# DigitalWave.net
KiCad netlist of a schematic drawn in EAGLE
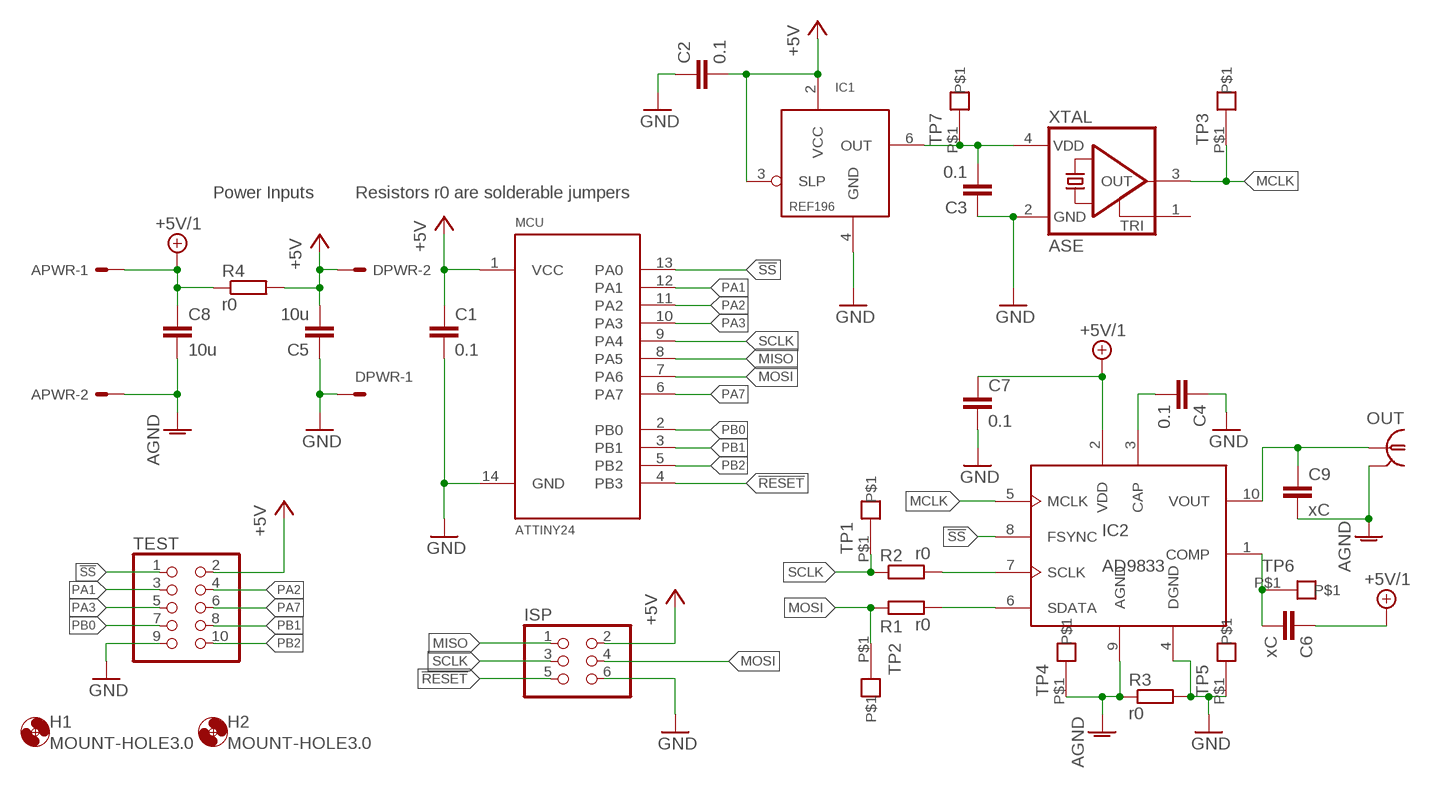
[diagram p0: schematic, sheet 1]

(export (version "E")
  (design (tool "Eeschema 10.0.6"))
  (components
    (comp (ref "APWR")
      (value "22-27-2021-02")
      (footprint "eagle-import:6410-02")
      (libsource (lib "eagle-import") (part "22-?-0227-2021"))
    )
    (comp (ref "C1")
      (value "0.1")
      (footprint "eagle-import:C0805")
      (libsource (lib "eagle-import") (part "resistor_348_C-EUC0805"))
    )
    (comp (ref "C2")
      (value "0.1")
      (footprint "eagle-import:C0603")
      (libsource (lib "eagle-import") (part "resistor_348_C-EUC0603"))
    )
    (comp (ref "C3")
      (value "0.1")
      (footprint "eagle-import:C0603")
      (libsource (lib "eagle-import") (part "resistor_348_C-EUC0603"))
    )
    (comp (ref "C4")
      (value "0.1")
      (footprint "eagle-import:C0603")
      (libsource (lib "eagle-import") (part "resistor_348_C-EUC0603"))
    )
    (comp (ref "C5")
      (value "10u")
      (footprint "eagle-import:C0805")
      (libsource (lib "eagle-import") (part "resistor_348_C-EUC0805"))
    )
    (comp (ref "C6")
      (value "xC")
      (footprint "eagle-import:C0805")
      (libsource (lib "eagle-import") (part "resistor_348_C-EUC0805"))
    )
    (comp (ref "C7")
      (value "0.1")
      (footprint "eagle-import:C0603")
      (libsource (lib "eagle-import") (part "resistor_348_C-EUC0603"))
    )
    (comp (ref "C8")
      (value "10u")
      (footprint "eagle-import:C0805")
      (libsource (lib "eagle-import") (part "resistor_348_C-EUC0805"))
    )
    (comp (ref "C9")
      (value "xC")
      (footprint "eagle-import:C0805")
      (libsource (lib "eagle-import") (part "C-EUC0805"))
    )
    (comp (ref "DPWR")
      (value "22-27-2021-02")
      (footprint "eagle-import:6410-02")
      (libsource (lib "eagle-import") (part "22-?-0227-2021"))
    )
    (comp (ref "H1")
      (value "MOUNT-HOLE3.0")
      (footprint "eagle-import:3,0")
      (libsource (lib "eagle-import") (part "MOUNT-HOLE3.0"))
    )
    (comp (ref "H2")
      (value "MOUNT-HOLE3.0")
      (footprint "eagle-import:3,0")
      (libsource (lib "eagle-import") (part "MOUNT-HOLE3.0"))
    )
    (comp (ref "IC1")
      (value "REF196")
      (footprint "eagle-import:SO08")
      (libsource (lib "eagle-import") (part "REF19XS"))
    )
    (comp (ref "IC2")
      (value "AD9833")
      (footprint "eagle-import:MSOP10")
      (libsource (lib "eagle-import") (part "AD9833/7"))
    )
    (comp (ref "ISP")
      (value "PINHD-2X3")
      (footprint "eagle-import:2X03")
      (libsource (lib "eagle-import") (part "PINHD-2X3"))
    )
    (comp (ref "MCU")
      (value "ATTINY24")
      (footprint "eagle-import:SO14")
      (libsource (lib "eagle-import") (part "ATTINY24ASO14"))
    )
    (comp (ref "OUT")
      (value "LTI-SASF54GT")
      (footprint "eagle-import:LTI-SASF54GT")
      (libsource (lib "eagle-import") (part "LTI-SASF54GT"))
    )
    (comp (ref "R1")
      (value "r0")
      (footprint "eagle-import:R0402")
      (libsource (lib "eagle-import") (part "R-EU_R0402"))
    )
    (comp (ref "R2")
      (value "r0")
      (footprint "eagle-import:R0402")
      (libsource (lib "eagle-import") (part "R-EU_R0402"))
    )
    (comp (ref "R3")
      (value "r0")
      (footprint "eagle-import:R0402")
      (libsource (lib "eagle-import") (part "R-EU_R0402"))
    )
    (comp (ref "R4")
      (value "r0")
      (footprint "eagle-import:R0402")
      (libsource (lib "eagle-import") (part "R-EU_R0402"))
    )
    (comp (ref "TEST")
      (value "PINHD-2X5")
      (footprint "eagle-import:2X05")
      (libsource (lib "eagle-import") (part "PINHD-2X5"))
    )
    (comp (ref "TP1")
      (value "TESTPOINT")
      (footprint "eagle-import:TESTPOINT")
      (libsource (lib "eagle-import") (part "TESTPOINT"))
    )
    (comp (ref "TP2")
      (value "TESTPOINT")
      (footprint "eagle-import:TESTPOINT")
      (libsource (lib "eagle-import") (part "TESTPOINT"))
    )
    (comp (ref "TP3")
      (value "TESTPOINT")
      (footprint "eagle-import:TESTPOINT")
      (libsource (lib "eagle-import") (part "TESTPOINT"))
    )
    (comp (ref "TP4")
      (value "TESTPOINT")
      (footprint "eagle-import:TESTPOINT")
      (libsource (lib "eagle-import") (part "TESTPOINT"))
    )
    (comp (ref "TP5")
      (value "TESTPOINT")
      (footprint "eagle-import:TESTPOINT")
      (libsource (lib "eagle-import") (part "TESTPOINT"))
    )
    (comp (ref "TP6")
      (value "TESTPOINT")
      (footprint "eagle-import:TESTPOINT")
      (libsource (lib "eagle-import") (part "TESTPOINT"))
    )
    (comp (ref "TP7")
      (value "TESTPOINT")
      (footprint "eagle-import:TESTPOINT")
      (libsource (lib "eagle-import") (part "TESTPOINT"))
    )
    (comp (ref "XTAL")
      (value "ASE")
      (footprint "eagle-import:ASE")
      (libsource (lib "eagle-import") (part "ASE"))
    )
  )
  (nets
    (net (code "1") (name "+5V") (class "Default")
      (node (ref "C1") (pin "1") (pinfunction "1_1") (pintype "passive"))
      (node (ref "C2") (pin "2") (pinfunction "2_2") (pintype "passive"))
      (node (ref "C5") (pin "2") (pinfunction "2_2") (pintype "passive"))
      (node (ref "DPWR") (pin "2") (pinfunction "S_2") (pintype "passive"))
      (node (ref "IC1") (pin "2") (pinfunction "VCC_2") (pintype "power_in"))
      (node (ref "IC1") (pin "3") (pinfunction "SLP_3") (pintype "input"))
      (node (ref "ISP") (pin "2") (pinfunction "2_2") (pintype "passive"))
      (node (ref "MCU") (pin "1") (pinfunction "VCC_1") (pintype "bidirectional"))
      (node (ref "R4") (pin "2") (pinfunction "2_2") (pintype "passive"))
      (node (ref "TEST") (pin "2") (pinfunction "2_2") (pintype "passive"))
    )
    (net (code "2") (name "+5V{slash}1") (class "Default")
      (node (ref "APWR") (pin "1") (pinfunction "S_1") (pintype "passive"))
      (node (ref "C6") (pin "1") (pinfunction "1_1") (pintype "passive"))
      (node (ref "C7") (pin "1") (pinfunction "1_1") (pintype "passive"))
      (node (ref "C8") (pin "1") (pinfunction "1_1") (pintype "passive"))
      (node (ref "IC2") (pin "2") (pinfunction "VDD_2") (pintype "bidirectional"))
      (node (ref "R4") (pin "1") (pinfunction "1_1") (pintype "passive"))
    )
    (net (code "3") (name "/~{RESET}") (class "Default")
      (node (ref "ISP") (pin "5") (pinfunction "5_5") (pintype "passive"))
      (node (ref "MCU") (pin "4") (pinfunction "PB3_4") (pintype "bidirectional"))
    )
    (net (code "4") (name "/~{SS}") (class "Default")
      (node (ref "IC2") (pin "8") (pinfunction "FSYNC_8") (pintype "bidirectional"))
      (node (ref "MCU") (pin "13") (pinfunction "PA0_13") (pintype "bidirectional"))
      (node (ref "TEST") (pin "1") (pinfunction "1_1") (pintype "passive"))
    )
    (net (code "5") (name "AGND") (class "Default")
      (node (ref "APWR") (pin "2") (pinfunction "S_2") (pintype "passive"))
      (node (ref "C8") (pin "2") (pinfunction "2_2") (pintype "passive"))
      (node (ref "C9") (pin "2") (pinfunction "2_2") (pintype "passive"))
      (node (ref "IC2") (pin "9") (pinfunction "AGND_9") (pintype "bidirectional"))
      (node (ref "OUT") (pin "2") (pinfunction "2_2") (pintype "passive"))
      (node (ref "OUT") (pin "3") (pinfunction "2_3") (pintype "passive"))
      (node (ref "OUT") (pin "4") (pinfunction "2_4") (pintype "passive"))
      (node (ref "OUT") (pin "5") (pinfunction "2_5") (pintype "passive"))
      (node (ref "R3") (pin "1") (pinfunction "1_1") (pintype "passive"))
      (node (ref "TP4") (pin "P$1") (pinfunction "P$1_P$1") (pintype "bidirectional"))
    )
    (net (code "6") (name "GND") (class "Default")
      (node (ref "C1") (pin "2") (pinfunction "2_2") (pintype "passive"))
      (node (ref "C2") (pin "1") (pinfunction "1_1") (pintype "passive"))
      (node (ref "C3") (pin "1") (pinfunction "1_1") (pintype "passive"))
      (node (ref "C4") (pin "1") (pinfunction "1_1") (pintype "passive"))
      (node (ref "C5") (pin "1") (pinfunction "1_1") (pintype "passive"))
      (node (ref "C7") (pin "2") (pinfunction "2_2") (pintype "passive"))
      (node (ref "DPWR") (pin "1") (pinfunction "S_1") (pintype "passive"))
      (node (ref "IC1") (pin "4") (pinfunction "GND_4") (pintype "power_in"))
      (node (ref "IC2") (pin "4") (pinfunction "DGND_4") (pintype "bidirectional"))
      (node (ref "ISP") (pin "6") (pinfunction "6_6") (pintype "passive"))
      (node (ref "MCU") (pin "14") (pinfunction "GND_14") (pintype "bidirectional"))
      (node (ref "R3") (pin "2") (pinfunction "2_2") (pintype "passive"))
      (node (ref "TEST") (pin "9") (pinfunction "9_9") (pintype "passive"))
      (node (ref "TP5") (pin "P$1") (pinfunction "P$1_P$1") (pintype "bidirectional"))
      (node (ref "XTAL") (pin "2") (pinfunction "GND_2") (pintype "power_in"))
    )
    (net (code "7") (name "MCLK") (class "Default")
      (node (ref "IC2") (pin "5") (pinfunction "MCLK_5") (pintype "bidirectional"))
      (node (ref "TP3") (pin "P$1") (pinfunction "P$1_P$1") (pintype "bidirectional"))
      (node (ref "XTAL") (pin "3") (pinfunction "OUT_3") (pintype "output"))
    )
    (net (code "8") (name "MISO") (class "Default")
      (node (ref "ISP") (pin "1") (pinfunction "1_1") (pintype "passive"))
      (node (ref "MCU") (pin "8") (pinfunction "PA5_8") (pintype "bidirectional"))
    )
    (net (code "9") (name "MOSI") (class "Default")
      (node (ref "ISP") (pin "4") (pinfunction "4_4") (pintype "passive"))
      (node (ref "MCU") (pin "7") (pinfunction "PA6_7") (pintype "bidirectional"))
      (node (ref "R1") (pin "1") (pinfunction "1_1") (pintype "passive"))
      (node (ref "TP2") (pin "P$1") (pinfunction "P$1_P$1") (pintype "bidirectional"))
    )
    (net (code "10") (name "Net-(IC1-OUT)") (class "Default")
      (node (ref "C3") (pin "2") (pinfunction "2_2") (pintype "passive"))
      (node (ref "IC1") (pin "6") (pinfunction "OUT_6") (pintype "output"))
      (node (ref "TP7") (pin "P$1") (pinfunction "P$1_P$1") (pintype "bidirectional"))
      (node (ref "XTAL") (pin "4") (pinfunction "VDD_4") (pintype "power_in"))
    )
    (net (code "11") (name "Net-(IC2-CAP)") (class "Default")
      (node (ref "C4") (pin "2") (pinfunction "2_2") (pintype "passive"))
      (node (ref "IC2") (pin "3") (pinfunction "CAP_3") (pintype "bidirectional"))
    )
    (net (code "12") (name "Net-(IC2-COMP)") (class "Default")
      (node (ref "C6") (pin "2") (pinfunction "2_2") (pintype "passive"))
      (node (ref "IC2") (pin "1") (pinfunction "COMP_1") (pintype "bidirectional"))
      (node (ref "TP6") (pin "P$1") (pinfunction "P$1_P$1") (pintype "bidirectional"))
    )
    (net (code "13") (name "Net-(IC2-SCLK)") (class "Default")
      (node (ref "IC2") (pin "7") (pinfunction "SCLK_7") (pintype "bidirectional"))
      (node (ref "R2") (pin "2") (pinfunction "2_2") (pintype "passive"))
    )
    (net (code "14") (name "Net-(IC2-SDATA)") (class "Default")
      (node (ref "IC2") (pin "6") (pinfunction "SDATA_6") (pintype "bidirectional"))
      (node (ref "R1") (pin "2") (pinfunction "2_2") (pintype "passive"))
    )
    (net (code "15") (name "Net-(IC2-VOUT)") (class "Default")
      (node (ref "C9") (pin "1") (pinfunction "1_1") (pintype "passive"))
      (node (ref "IC2") (pin "10") (pinfunction "VOUT_10") (pintype "bidirectional"))
      (node (ref "OUT") (pin "1") (pinfunction "1_1") (pintype "passive"))
    )
    (net (code "16") (name "PA1") (class "Default")
      (node (ref "MCU") (pin "12") (pinfunction "PA1_12") (pintype "bidirectional"))
      (node (ref "TEST") (pin "3") (pinfunction "3_3") (pintype "passive"))
    )
    (net (code "17") (name "PA2") (class "Default")
      (node (ref "MCU") (pin "11") (pinfunction "PA2_11") (pintype "bidirectional"))
      (node (ref "TEST") (pin "4") (pinfunction "4_4") (pintype "passive"))
    )
    (net (code "18") (name "PA3") (class "Default")
      (node (ref "MCU") (pin "10") (pinfunction "PA3_10") (pintype "bidirectional"))
      (node (ref "TEST") (pin "5") (pinfunction "5_5") (pintype "passive"))
    )
    (net (code "19") (name "PA7") (class "Default")
      (node (ref "MCU") (pin "6") (pinfunction "PA7_6") (pintype "bidirectional"))
      (node (ref "TEST") (pin "6") (pinfunction "6_6") (pintype "passive"))
    )
    (net (code "20") (name "PB0") (class "Default")
      (node (ref "MCU") (pin "2") (pinfunction "PB0_2") (pintype "bidirectional"))
      (node (ref "TEST") (pin "7") (pinfunction "7_7") (pintype "passive"))
    )
    (net (code "21") (name "PB1") (class "Default")
      (node (ref "MCU") (pin "3") (pinfunction "PB1_3") (pintype "bidirectional"))
      (node (ref "TEST") (pin "8") (pinfunction "8_8") (pintype "passive"))
    )
    (net (code "22") (name "PB2") (class "Default")
      (node (ref "MCU") (pin "5") (pinfunction "PB2_5") (pintype "bidirectional"))
      (node (ref "TEST") (pin "10") (pinfunction "10_10") (pintype "passive"))
    )
    (net (code "23") (name "SCLK") (class "Default")
      (node (ref "ISP") (pin "3") (pinfunction "3_3") (pintype "passive"))
      (node (ref "MCU") (pin "9") (pinfunction "PA4_9") (pintype "bidirectional"))
      (node (ref "R2") (pin "1") (pinfunction "1_1") (pintype "passive"))
      (node (ref "TP1") (pin "P$1") (pinfunction "P$1_P$1") (pintype "bidirectional"))
    )
    (net (code "24") (name "unconnected-(XTAL-TRI-Pad1)") (class "Default")
      (node (ref "XTAL") (pin "1") (pinfunction "TRI_1") (pintype "input"))
    )
  )
)
